# Pressure_sensor_prototype_2.net
KiCad netlist of a schematic drawn in EAGLE
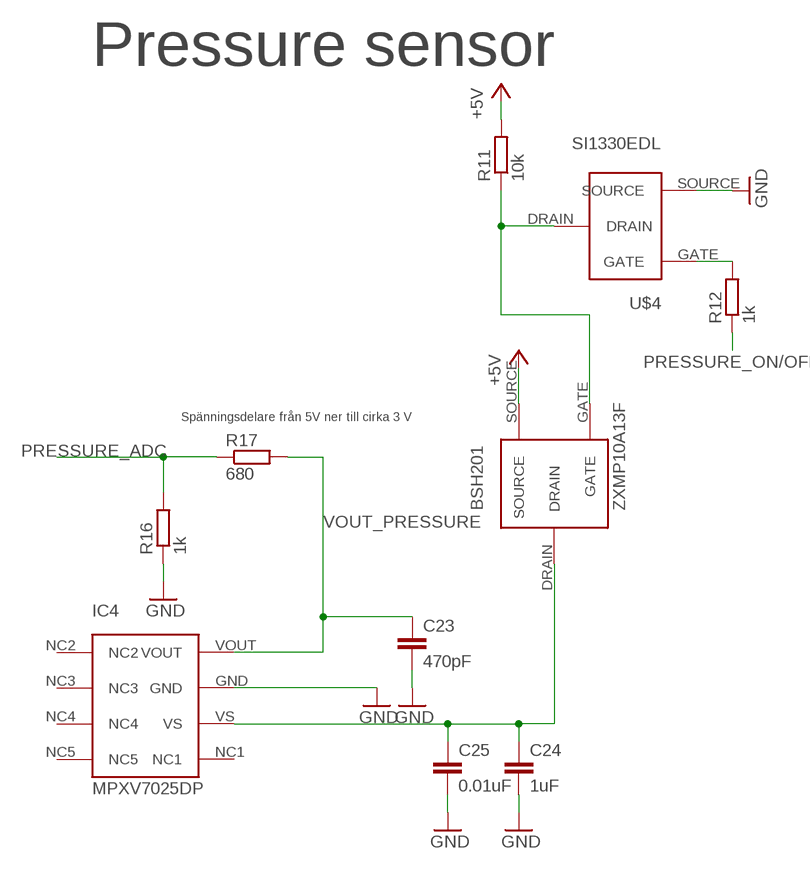
[diagram p0: schematic, sheet 1]

(export (version "E")
  (design (tool "Eeschema 10.0.6"))
  (components
    (comp (ref "BSH201")
      (value "ZXMP10A13F")
      (footprint "eagle-import:P-CHANNEL")
      (libsource (lib "eagle-import") (part "ZXMP10A13F"))
    )
    (comp (ref "C23")
      (value "470pF")
      (footprint "eagle-import:C0805")
      (libsource (lib "eagle-import") (part "C-EUC0805"))
    )
    (comp (ref "C24")
      (value "1uF")
      (footprint "eagle-import:C0805")
      (libsource (lib "eagle-import") (part "C-EUC0805"))
    )
    (comp (ref "C25")
      (value "0.01uF")
      (footprint "eagle-import:C0805")
      (libsource (lib "eagle-import") (part "C-EUC0805"))
    )
    (comp (ref "IC4")
      (value "MPXV7025DP")
      (footprint "eagle-import:CASE1351-01")
      (libsource (lib "eagle-import") (part "MPXV7025DP"))
    )
    (comp (ref "R11")
      (value "10k")
      (footprint "eagle-import:R0805")
      (libsource (lib "eagle-import") (part "R-EU_R0805"))
    )
    (comp (ref "R12")
      (value "1k")
      (footprint "eagle-import:R0805")
      (libsource (lib "eagle-import") (part "R-EU_R0805"))
    )
    (comp (ref "R16")
      (value "1k")
      (footprint "eagle-import:R0805")
      (libsource (lib "eagle-import") (part "R-EU_R0805"))
    )
    (comp (ref "R17")
      (value "680")
      (footprint "eagle-import:R0805")
      (libsource (lib "eagle-import") (part "R-EU_R0805"))
    )
    (comp (ref "U$4")
      (value "SI1330EDL")
      (footprint "eagle-import:SOT-323")
      (libsource (lib "eagle-import") (part "SI1330EDL"))
    )
  )
  (nets
    (net (code "1") (name "+5V") (class "Default")
      (node (ref "BSH201") (pin "SOURCE") (pinfunction "SOURCE_SOURCE") (pintype "bidirectional"))
      (node (ref "R11") (pin "2") (pinfunction "2_2") (pintype "passive"))
    )
    (net (code "2") (name "/PRESSURE_ADC") (class "Default")
      (node (ref "R16") (pin "2") (pinfunction "2_2") (pintype "passive"))
      (node (ref "R17") (pin "1") (pinfunction "1_1") (pintype "passive"))
    )
    (net (code "3") (name "/PRESSURE_ON{slash}OFF") (class "Default")
      (node (ref "R12") (pin "1") (pinfunction "1_1") (pintype "passive"))
    )
    (net (code "4") (name "/VOUT_PRESSURE") (class "Default")
      (node (ref "C23") (pin "1") (pinfunction "1_1") (pintype "passive"))
      (node (ref "IC4") (pin "VOUT") (pinfunction "VOUT_VOUT") (pintype "bidirectional"))
      (node (ref "R17") (pin "2") (pinfunction "2_2") (pintype "passive"))
    )
    (net (code "5") (name "GND") (class "Default")
      (node (ref "C23") (pin "2") (pinfunction "2_2") (pintype "passive"))
      (node (ref "C24") (pin "2") (pinfunction "2_2") (pintype "passive"))
      (node (ref "C25") (pin "2") (pinfunction "2_2") (pintype "passive"))
      (node (ref "IC4") (pin "GND") (pinfunction "GND_GND") (pintype "bidirectional"))
      (node (ref "R16") (pin "1") (pinfunction "1_1") (pintype "passive"))
      (node (ref "U$4") (pin "SOURCE") (pinfunction "SOURCE_SOURCE") (pintype "bidirectional"))
    )
    (net (code "6") (name "Net-(BSH201-PadDRAIN)") (class "Default")
      (node (ref "BSH201") (pin "DRAIN") (pinfunction "DRAIN_DRAIN") (pintype "bidirectional"))
      (node (ref "C24") (pin "1") (pinfunction "1_1") (pintype "passive"))
      (node (ref "C25") (pin "1") (pinfunction "1_1") (pintype "passive"))
      (node (ref "IC4") (pin "VS") (pinfunction "VS_VS") (pintype "bidirectional"))
    )
    (net (code "7") (name "Net-(BSH201-PadGATE)") (class "Default")
      (node (ref "BSH201") (pin "GATE") (pinfunction "GATE_GATE") (pintype "bidirectional"))
      (node (ref "R11") (pin "1") (pinfunction "1_1") (pintype "passive"))
      (node (ref "U$4") (pin "DRAIN") (pinfunction "DRAIN_DRAIN") (pintype "bidirectional"))
    )
    (net (code "8") (name "Net-(R12-Pad2)") (class "Default")
      (node (ref "R12") (pin "2") (pinfunction "2_2") (pintype "passive"))
      (node (ref "U$4") (pin "GATE") (pinfunction "GATE_GATE") (pintype "bidirectional"))
    )
    (net (code "9") (name "unconnected-(IC4-PadNC1)") (class "Default")
      (node (ref "IC4") (pin "NC1") (pinfunction "NC1_NC1") (pintype "bidirectional"))
    )
    (net (code "10") (name "unconnected-(IC4-PadNC2)") (class "Default")
      (node (ref "IC4") (pin "NC2") (pinfunction "NC2_NC2") (pintype "bidirectional"))
    )
    (net (code "11") (name "unconnected-(IC4-PadNC3)") (class "Default")
      (node (ref "IC4") (pin "NC3") (pinfunction "NC3_NC3") (pintype "bidirectional"))
    )
    (net (code "12") (name "unconnected-(IC4-PadNC4)") (class "Default")
      (node (ref "IC4") (pin "NC4") (pinfunction "NC4_NC4") (pintype "bidirectional"))
    )
    (net (code "13") (name "unconnected-(IC4-PadNC5)") (class "Default")
      (node (ref "IC4") (pin "NC5") (pinfunction "NC5_NC5") (pintype "bidirectional"))
    )
  )
)
